# rony_servo.net
KiCad netlist of a schematic drawn in EAGLE
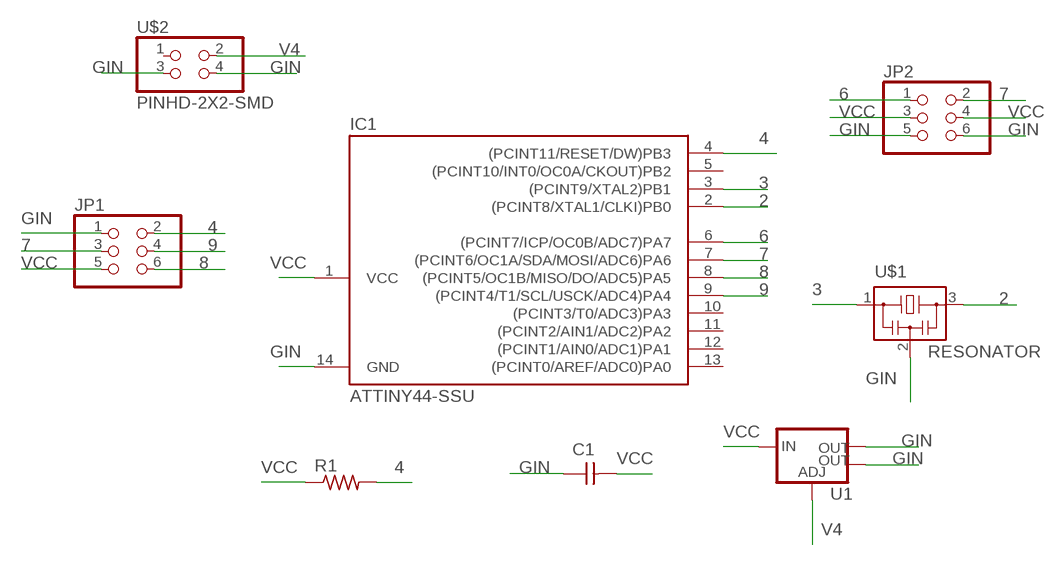
[diagram p0: schematic, sheet 1]

(export (version "E")
  (design (tool "Eeschema 10.0.6"))
  (components
    (comp (ref "C1")
      (value "CAP-UNPOLARIZEDFAB")
      (footprint "eagle-import:C1206FAB")
      (libsource (lib "eagle-import") (part "CAP-UNPOLARIZEDFAB"))
    )
    (comp (ref "IC1")
      (value "ATTINY44-SSU")
      (footprint "eagle-import:SOIC14")
      (libsource (lib "eagle-import") (part "ATTINY44-SSU"))
    )
    (comp (ref "JP1")
      (value "PINHD-2X3-SMD")
      (footprint "eagle-import:2X03SMD")
      (libsource (lib "eagle-import") (part "PINHD-2X3-SMD"))
    )
    (comp (ref "JP2")
      (value "PINHD-2X3-SMD")
      (footprint "eagle-import:2X03SMD")
      (libsource (lib "eagle-import") (part "PINHD-2X3-SMD"))
    )
    (comp (ref "R1")
      (value "RES-US1206FAB")
      (footprint "eagle-import:R1206FAB")
      (libsource (lib "eagle-import") (part "RES-US1206FAB"))
    )
    (comp (ref "U$1")
      (value "RESONATOR")
      (footprint "eagle-import:EFOBM")
      (libsource (lib "eagle-import") (part "RESONATOR"))
    )
    (comp (ref "U$2")
      (value "PINHD-2X2-SMD")
      (footprint "eagle-import:2X02SMD")
      (libsource (lib "eagle-import") (part "PINHD-2X2-SMD"))
    )
    (comp (ref "U1")
      (value "V_REG_LM1117SOT223")
      (footprint "eagle-import:SOT223")
      (libsource (lib "eagle-import") (part "V_REG_LM1117SOT223"))
    )
  )
  (nets
    (net (code "1") (name "/2") (class "Default")
      (node (ref "IC1") (pin "2") (pinfunction "(PCINT8/XTAL1/CLKI)PB0_2") (pintype "bidirectional"))
      (node (ref "U$1") (pin "3") (pinfunction "3_3") (pintype "passive"))
    )
    (net (code "2") (name "/3") (class "Default")
      (node (ref "IC1") (pin "3") (pinfunction "(PCINT9/XTAL2)PB1_3") (pintype "bidirectional"))
      (node (ref "U$1") (pin "1") (pinfunction "1_1") (pintype "passive"))
    )
    (net (code "3") (name "/4") (class "Default")
      (node (ref "IC1") (pin "4") (pinfunction "(PCINT11/RESET/DW)PB3_4") (pintype "bidirectional"))
      (node (ref "JP1") (pin "2") (pinfunction "2_2") (pintype "passive"))
      (node (ref "R1") (pin "2") (pinfunction "2_2") (pintype "passive"))
    )
    (net (code "4") (name "/6") (class "Default")
      (node (ref "IC1") (pin "6") (pinfunction "(PCINT7/ICP/OC0B/ADC7)PA7_6") (pintype "bidirectional"))
      (node (ref "JP2") (pin "1") (pinfunction "1_1") (pintype "passive"))
    )
    (net (code "5") (name "/7") (class "Default")
      (node (ref "IC1") (pin "7") (pinfunction "(PCINT6/OC1A/SDA/MOSI/ADC6)PA6_7") (pintype "bidirectional"))
      (node (ref "JP1") (pin "3") (pinfunction "3_3") (pintype "passive"))
      (node (ref "JP2") (pin "2") (pinfunction "2_2") (pintype "passive"))
    )
    (net (code "6") (name "/8") (class "Default")
      (node (ref "IC1") (pin "8") (pinfunction "(PCINT5/OC1B/MISO/DO/ADC5)PA5_8") (pintype "bidirectional"))
      (node (ref "JP1") (pin "6") (pinfunction "6_6") (pintype "passive"))
    )
    (net (code "7") (name "/9") (class "Default")
      (node (ref "IC1") (pin "9") (pinfunction "(PCINT4/T1/SCL/USCK/ADC4)PA4_9") (pintype "bidirectional"))
      (node (ref "JP1") (pin "4") (pinfunction "4_4") (pintype "passive"))
    )
    (net (code "8") (name "/GIN") (class "Default")
      (node (ref "C1") (pin "1") (pinfunction "1_1") (pintype "passive"))
      (node (ref "IC1") (pin "14") (pinfunction "GND_14") (pintype "power_in"))
      (node (ref "JP1") (pin "1") (pinfunction "1_1") (pintype "passive"))
      (node (ref "JP2") (pin "5") (pinfunction "5_5") (pintype "passive"))
      (node (ref "JP2") (pin "6") (pinfunction "6_6") (pintype "passive"))
      (node (ref "U$1") (pin "2") (pinfunction "2_2") (pintype "passive"))
      (node (ref "U$2") (pin "3") (pinfunction "3_3") (pintype "passive"))
      (node (ref "U$2") (pin "4") (pinfunction "4_4") (pintype "passive"))
      (node (ref "U1") (pin "2") (pinfunction "OUT_2") (pintype "output"))
      (node (ref "U1") (pin "4") (pinfunction "OUT_4") (pintype "output"))
    )
    (net (code "9") (name "/V4") (class "Default")
      (node (ref "U$2") (pin "2") (pinfunction "2_2") (pintype "passive"))
      (node (ref "U1") (pin "1") (pinfunction "ADJ_1") (pintype "input"))
    )
    (net (code "10") (name "/VCC") (class "Default")
      (node (ref "C1") (pin "2") (pinfunction "2_2") (pintype "passive"))
      (node (ref "IC1") (pin "1") (pinfunction "VCC_1") (pintype "power_in"))
      (node (ref "JP1") (pin "5") (pinfunction "5_5") (pintype "passive"))
      (node (ref "JP2") (pin "3") (pinfunction "3_3") (pintype "passive"))
      (node (ref "JP2") (pin "4") (pinfunction "4_4") (pintype "passive"))
      (node (ref "R1") (pin "1") (pinfunction "1_1") (pintype "passive"))
      (node (ref "U1") (pin "3") (pinfunction "IN_3") (pintype "input"))
    )
    (net (code "11") (name "unconnected-(IC1-(PCINT0{slash}AREF{slash}ADC0)PA0-Pad13)") (class "Default")
      (node (ref "IC1") (pin "13") (pinfunction "(PCINT0/AREF/ADC0)PA0_13") (pintype "bidirectional"))
    )
    (net (code "12") (name "unconnected-(IC1-(PCINT1{slash}AIN0{slash}ADC1)PA1-Pad12)") (class "Default")
      (node (ref "IC1") (pin "12") (pinfunction "(PCINT1/AIN0/ADC1)PA1_12") (pintype "bidirectional"))
    )
    (net (code "13") (name "unconnected-(IC1-(PCINT2{slash}AIN1{slash}ADC2)PA2-Pad11)") (class "Default")
      (node (ref "IC1") (pin "11") (pinfunction "(PCINT2/AIN1/ADC2)PA2_11") (pintype "bidirectional"))
    )
    (net (code "14") (name "unconnected-(IC1-(PCINT3{slash}T0{slash}ADC3)PA3-Pad10)") (class "Default")
      (node (ref "IC1") (pin "10") (pinfunction "(PCINT3/T0/ADC3)PA3_10") (pintype "bidirectional"))
    )
    (net (code "15") (name "unconnected-(IC1-(PCINT10{slash}INT0{slash}OC0A{slash}CKOUT)PB2-Pad5)") (class "Default")
      (node (ref "IC1") (pin "5") (pinfunction "(PCINT10/INT0/OC0A/CKOUT)PB2_5") (pintype "bidirectional"))
    )
    (net (code "16") (name "unconnected-(U$2-Pad1)") (class "Default")
      (node (ref "U$2") (pin "1") (pinfunction "1_1") (pintype "passive"))
    )
  )
)
